# adc_pi-dock.net
KiCad netlist of a schematic drawn in Altium Designer
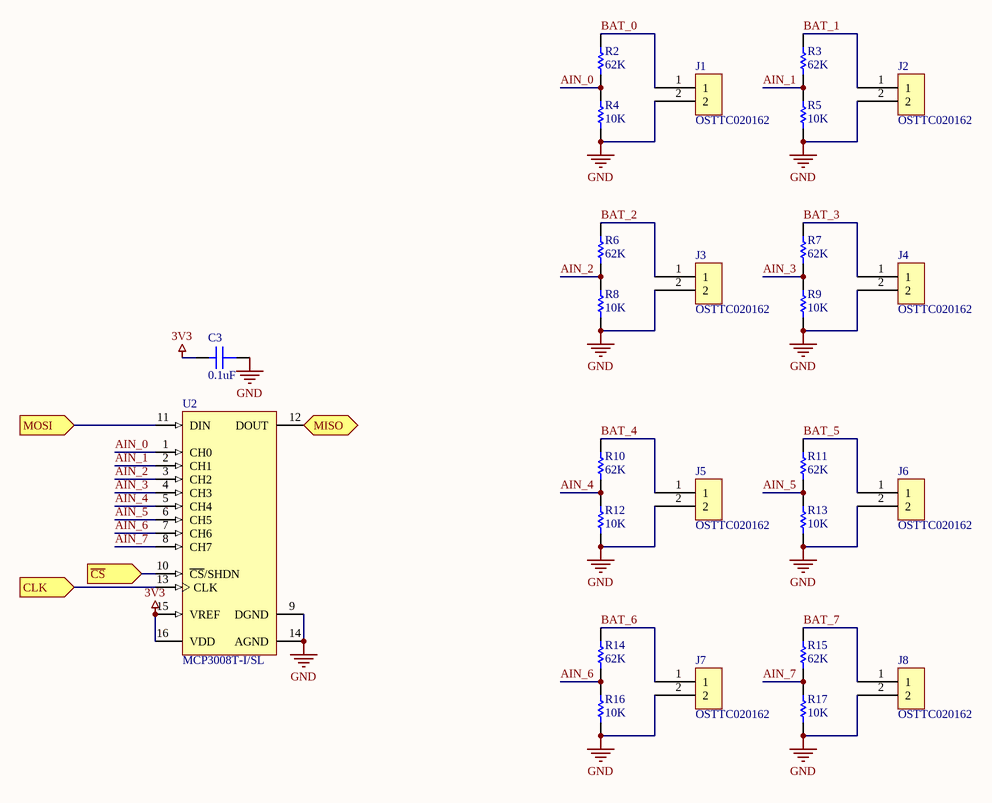
[diagram p0: adc_pi-dock.SchDoc]

(export (version "E")
  (design (tool "Eeschema 10.0.6"))
  (components
    (comp (ref "C3")
      (value "0.1uF")
      (footprint "CAP_8085")
      (description "SMD Chip Capacitor")
      (libsource (lib "[Asshat] Passives") (part "CHIP-CAP"))
    )
    (comp (ref "J1")
      (value "OSTTC020162")
      (footprint "DIP2_5MM_SCREWTERM")
      (description "ON SHORE TERMINAL BLOCK 5MM VERT 2POS PCB")
      (libsource (lib "[Asshat] Connectors") (part "OSTTC020162"))
    )
    (comp (ref "J2")
      (value "OSTTC020162")
      (footprint "DIP2_5MM_SCREWTERM")
      (description "ON SHORE TERMINAL BLOCK 5MM VERT 2POS PCB")
      (libsource (lib "[Asshat] Connectors") (part "OSTTC020162"))
    )
    (comp (ref "J3")
      (value "OSTTC020162")
      (footprint "DIP2_5MM_SCREWTERM")
      (description "ON SHORE TERMINAL BLOCK 5MM VERT 2POS PCB")
      (libsource (lib "[Asshat] Connectors") (part "OSTTC020162"))
    )
    (comp (ref "J4")
      (value "OSTTC020162")
      (footprint "DIP2_5MM_SCREWTERM")
      (description "ON SHORE TERMINAL BLOCK 5MM VERT 2POS PCB")
      (libsource (lib "[Asshat] Connectors") (part "OSTTC020162"))
    )
    (comp (ref "J5")
      (value "OSTTC020162")
      (footprint "DIP2_5MM_SCREWTERM")
      (description "ON SHORE TERMINAL BLOCK 5MM VERT 2POS PCB")
      (libsource (lib "[Asshat] Connectors") (part "OSTTC020162"))
    )
    (comp (ref "J6")
      (value "OSTTC020162")
      (footprint "DIP2_5MM_SCREWTERM")
      (description "ON SHORE TERMINAL BLOCK 5MM VERT 2POS PCB")
      (libsource (lib "[Asshat] Connectors") (part "OSTTC020162"))
    )
    (comp (ref "J7")
      (value "OSTTC020162")
      (footprint "DIP2_5MM_SCREWTERM")
      (description "ON SHORE TERMINAL BLOCK 5MM VERT 2POS PCB")
      (libsource (lib "[Asshat] Connectors") (part "OSTTC020162"))
    )
    (comp (ref "J8")
      (value "OSTTC020162")
      (footprint "DIP2_5MM_SCREWTERM")
      (description "ON SHORE TERMINAL BLOCK 5MM VERT 2POS PCB")
      (libsource (lib "[Asshat] Connectors") (part "OSTTC020162"))
    )
    (comp (ref "R2")
      (value "62K")
      (footprint "RES_8085")
      (description "SMD Chip Resistor")
      (libsource (lib "[Asshat] Passives") (part "CHIP-RES"))
    )
    (comp (ref "R3")
      (value "62K")
      (footprint "RES_8085")
      (description "SMD Chip Resistor")
      (libsource (lib "[Asshat] Passives") (part "CHIP-RES"))
    )
    (comp (ref "R4")
      (value "10K")
      (footprint "RES_8085")
      (description "SMD Chip Resistor")
      (libsource (lib "[Asshat] Passives") (part "CHIP-RES"))
    )
    (comp (ref "R5")
      (value "10K")
      (footprint "RES_8085")
      (description "SMD Chip Resistor")
      (libsource (lib "[Asshat] Passives") (part "CHIP-RES"))
    )
    (comp (ref "R6")
      (value "62K")
      (footprint "RES_8085")
      (description "SMD Chip Resistor")
      (libsource (lib "[Asshat] Passives") (part "CHIP-RES"))
    )
    (comp (ref "R7")
      (value "62K")
      (footprint "RES_8085")
      (description "SMD Chip Resistor")
      (libsource (lib "[Asshat] Passives") (part "CHIP-RES"))
    )
    (comp (ref "R8")
      (value "10K")
      (footprint "RES_8085")
      (description "SMD Chip Resistor")
      (libsource (lib "[Asshat] Passives") (part "CHIP-RES"))
    )
    (comp (ref "R9")
      (value "10K")
      (footprint "RES_8085")
      (description "SMD Chip Resistor")
      (libsource (lib "[Asshat] Passives") (part "CHIP-RES"))
    )
    (comp (ref "R10")
      (value "62K")
      (footprint "RES_8085")
      (description "SMD Chip Resistor")
      (libsource (lib "[Asshat] Passives") (part "CHIP-RES"))
    )
    (comp (ref "R11")
      (value "62K")
      (footprint "RES_8085")
      (description "SMD Chip Resistor")
      (libsource (lib "[Asshat] Passives") (part "CHIP-RES"))
    )
    (comp (ref "R12")
      (value "10K")
      (footprint "RES_8085")
      (description "SMD Chip Resistor")
      (libsource (lib "[Asshat] Passives") (part "CHIP-RES"))
    )
    (comp (ref "R13")
      (value "10K")
      (footprint "RES_8085")
      (description "SMD Chip Resistor")
      (libsource (lib "[Asshat] Passives") (part "CHIP-RES"))
    )
    (comp (ref "R14")
      (value "62K")
      (footprint "RES_8085")
      (description "SMD Chip Resistor")
      (libsource (lib "[Asshat] Passives") (part "CHIP-RES"))
    )
    (comp (ref "R15")
      (value "62K")
      (footprint "RES_8085")
      (description "SMD Chip Resistor")
      (libsource (lib "[Asshat] Passives") (part "CHIP-RES"))
    )
    (comp (ref "R16")
      (value "10K")
      (footprint "RES_8085")
      (description "SMD Chip Resistor")
      (libsource (lib "[Asshat] Passives") (part "CHIP-RES"))
    )
    (comp (ref "R17")
      (value "10K")
      (footprint "RES_8085")
      (description "SMD Chip Resistor")
      (libsource (lib "[Asshat] Passives") (part "CHIP-RES"))
    )
    (comp (ref "U2")
      (value "MCP3008T-I/SL")
      (footprint "SOIC-SL16_N")
      (libsource (lib "Altium Content Vault") (part "CON-ADC-MCP3008-16"))
    )
  )
  (nets
    (net (code "1") (name "/AIN_0") (class "Default")
      (node (ref "R2") (pin "1") (pinfunction "1_1") (pintype "passive"))
      (node (ref "R4") (pin "2") (pinfunction "2_2") (pintype "passive"))
      (node (ref "U2") (pin "1") (pinfunction "CH0_1") (pintype "input"))
    )
    (net (code "2") (name "/AIN_1") (class "Default")
      (node (ref "R3") (pin "1") (pinfunction "1_1") (pintype "passive"))
      (node (ref "R5") (pin "2") (pinfunction "2_2") (pintype "passive"))
      (node (ref "U2") (pin "2") (pinfunction "CH1_2") (pintype "input"))
    )
    (net (code "3") (name "/AIN_2") (class "Default")
      (node (ref "R6") (pin "1") (pinfunction "1_1") (pintype "passive"))
      (node (ref "R8") (pin "2") (pinfunction "2_2") (pintype "passive"))
      (node (ref "U2") (pin "3") (pinfunction "CH2_3") (pintype "input"))
    )
    (net (code "4") (name "/AIN_3") (class "Default")
      (node (ref "R7") (pin "1") (pinfunction "1_1") (pintype "passive"))
      (node (ref "R9") (pin "2") (pinfunction "2_2") (pintype "passive"))
      (node (ref "U2") (pin "4") (pinfunction "CH3_4") (pintype "input"))
    )
    (net (code "5") (name "/AIN_4") (class "Default")
      (node (ref "R10") (pin "1") (pinfunction "1_1") (pintype "passive"))
      (node (ref "R12") (pin "2") (pinfunction "2_2") (pintype "passive"))
      (node (ref "U2") (pin "5") (pinfunction "CH4_5") (pintype "input"))
    )
    (net (code "6") (name "/AIN_5") (class "Default")
      (node (ref "R11") (pin "1") (pinfunction "1_1") (pintype "passive"))
      (node (ref "R13") (pin "2") (pinfunction "2_2") (pintype "passive"))
      (node (ref "U2") (pin "6") (pinfunction "CH5_6") (pintype "input"))
    )
    (net (code "7") (name "/AIN_6") (class "Default")
      (node (ref "R14") (pin "1") (pinfunction "1_1") (pintype "passive"))
      (node (ref "R16") (pin "2") (pinfunction "2_2") (pintype "passive"))
      (node (ref "U2") (pin "7") (pinfunction "CH6_7") (pintype "input"))
    )
    (net (code "8") (name "/AIN_7") (class "Default")
      (node (ref "R15") (pin "1") (pinfunction "1_1") (pintype "passive"))
      (node (ref "R17") (pin "2") (pinfunction "2_2") (pintype "passive"))
      (node (ref "U2") (pin "8") (pinfunction "CH7_8") (pintype "input"))
    )
    (net (code "9") (name "/BAT_0") (class "Default")
      (node (ref "J1") (pin "1") (pinfunction "1_1") (pintype "passive"))
      (node (ref "R2") (pin "2") (pinfunction "2_2") (pintype "passive"))
    )
    (net (code "10") (name "/BAT_1") (class "Default")
      (node (ref "J2") (pin "1") (pinfunction "1_1") (pintype "passive"))
      (node (ref "R3") (pin "2") (pinfunction "2_2") (pintype "passive"))
    )
    (net (code "11") (name "/BAT_2") (class "Default")
      (node (ref "J3") (pin "1") (pinfunction "1_1") (pintype "passive"))
      (node (ref "R6") (pin "2") (pinfunction "2_2") (pintype "passive"))
    )
    (net (code "12") (name "/BAT_3") (class "Default")
      (node (ref "J4") (pin "1") (pinfunction "1_1") (pintype "passive"))
      (node (ref "R7") (pin "2") (pinfunction "2_2") (pintype "passive"))
    )
    (net (code "13") (name "/BAT_4") (class "Default")
      (node (ref "J5") (pin "1") (pinfunction "1_1") (pintype "passive"))
      (node (ref "R10") (pin "2") (pinfunction "2_2") (pintype "passive"))
    )
    (net (code "14") (name "/BAT_5") (class "Default")
      (node (ref "J6") (pin "1") (pinfunction "1_1") (pintype "passive"))
      (node (ref "R11") (pin "2") (pinfunction "2_2") (pintype "passive"))
    )
    (net (code "15") (name "/BAT_6") (class "Default")
      (node (ref "J7") (pin "1") (pinfunction "1_1") (pintype "passive"))
      (node (ref "R14") (pin "2") (pinfunction "2_2") (pintype "passive"))
    )
    (net (code "16") (name "/BAT_7") (class "Default")
      (node (ref "J8") (pin "1") (pinfunction "1_1") (pintype "passive"))
      (node (ref "R15") (pin "2") (pinfunction "2_2") (pintype "passive"))
    )
    (net (code "17") (name "/CLK") (class "Default")
      (node (ref "U2") (pin "13") (pinfunction "CLK_13") (pintype "input"))
    )
    (net (code "18") (name "/MISO") (class "Default")
      (node (ref "U2") (pin "12") (pinfunction "DOUT_12") (pintype "tri_state"))
    )
    (net (code "19") (name "/MOSI") (class "Default")
      (node (ref "U2") (pin "11") (pinfunction "DIN_11") (pintype "input"))
    )
    (net (code "20") (name "/~{CS}") (class "Default")
      (node (ref "U2") (pin "10") (pinfunction "~{CS}/SHDN_10") (pintype "input"))
    )
    (net (code "21") (name "3V3") (class "Default")
      (node (ref "C3") (pin "2") (pinfunction "2_2") (pintype "passive"))
      (node (ref "U2") (pin "15") (pinfunction "VREF_15") (pintype "input"))
      (node (ref "U2") (pin "16") (pinfunction "VDD_16") (pintype "power_in"))
    )
    (net (code "22") (name "GND") (class "Default")
      (node (ref "C3") (pin "1") (pinfunction "1_1") (pintype "passive"))
      (node (ref "J1") (pin "2") (pinfunction "2_2") (pintype "passive"))
      (node (ref "J2") (pin "2") (pinfunction "2_2") (pintype "passive"))
      (node (ref "J3") (pin "2") (pinfunction "2_2") (pintype "passive"))
      (node (ref "J4") (pin "2") (pinfunction "2_2") (pintype "passive"))
      (node (ref "J5") (pin "2") (pinfunction "2_2") (pintype "passive"))
      (node (ref "J6") (pin "2") (pinfunction "2_2") (pintype "passive"))
      (node (ref "J7") (pin "2") (pinfunction "2_2") (pintype "passive"))
      (node (ref "J8") (pin "2") (pinfunction "2_2") (pintype "passive"))
      (node (ref "R12") (pin "1") (pinfunction "1_1") (pintype "passive"))
      (node (ref "R13") (pin "1") (pinfunction "1_1") (pintype "passive"))
      (node (ref "R16") (pin "1") (pinfunction "1_1") (pintype "passive"))
      (node (ref "R17") (pin "1") (pinfunction "1_1") (pintype "passive"))
      (node (ref "R4") (pin "1") (pinfunction "1_1") (pintype "passive"))
      (node (ref "R5") (pin "1") (pinfunction "1_1") (pintype "passive"))
      (node (ref "R8") (pin "1") (pinfunction "1_1") (pintype "passive"))
      (node (ref "R9") (pin "1") (pinfunction "1_1") (pintype "passive"))
      (node (ref "U2") (pin "14") (pinfunction "AGND_14") (pintype "power_in"))
      (node (ref "U2") (pin "9") (pinfunction "DGND_9") (pintype "power_in"))
    )
  )
)
